# Power.net
KiCad netlist of a schematic drawn in Altium Designer
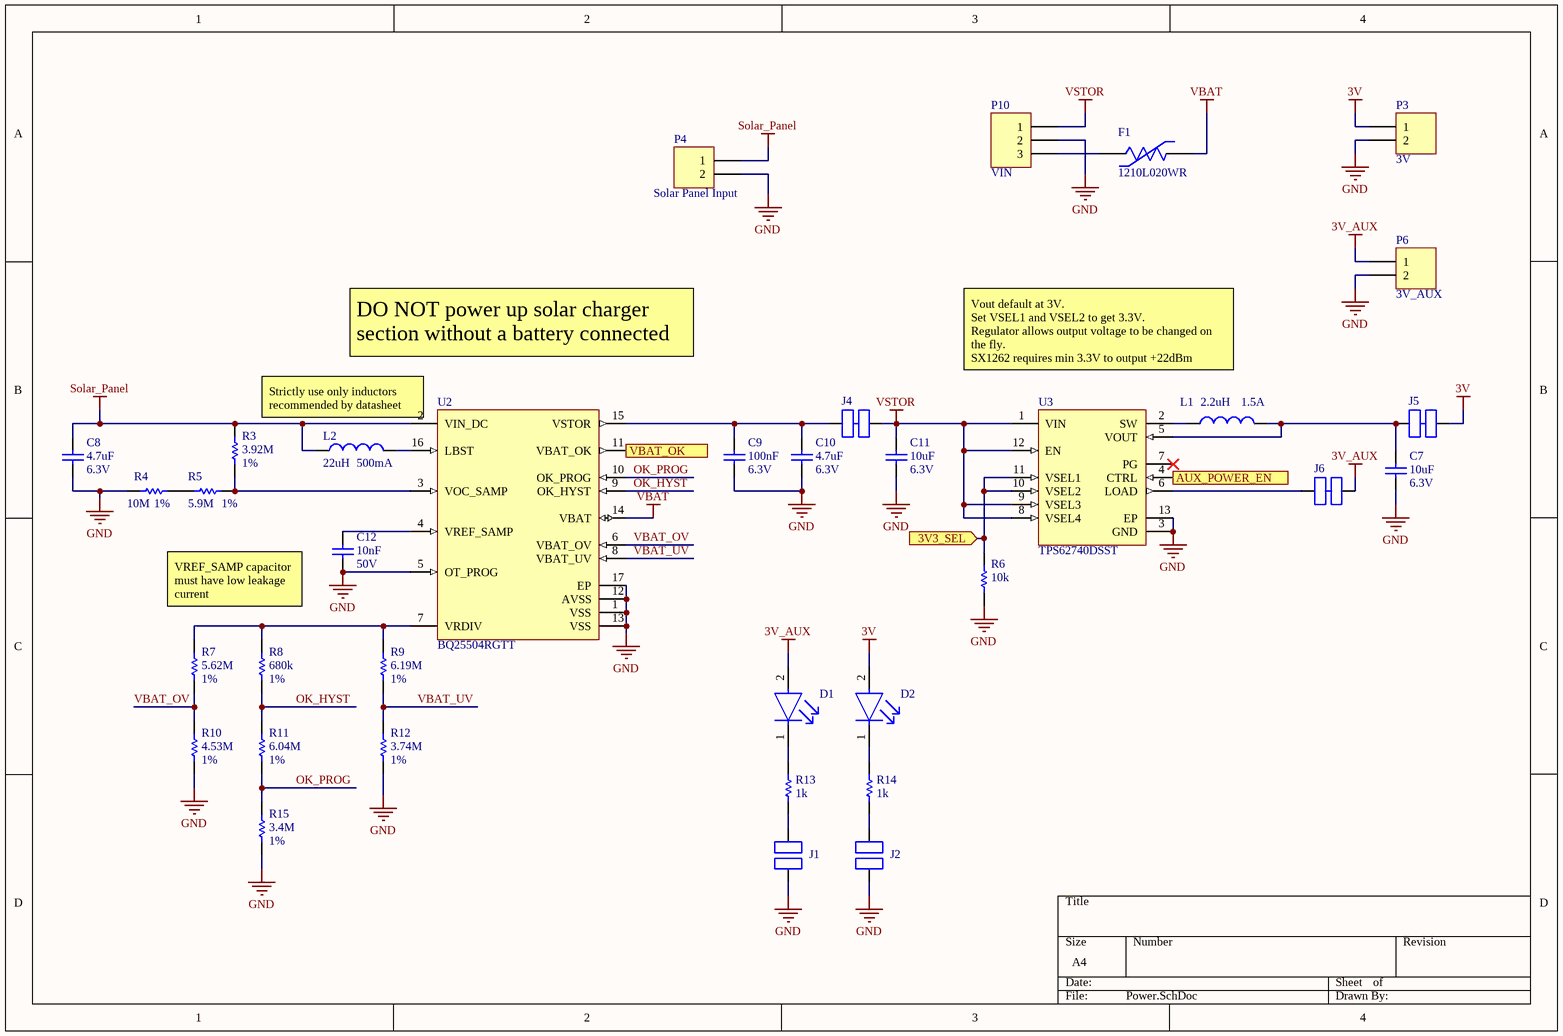
[diagram p0: Power.SchDoc]

(export (version "E")
  (design (tool "Eeschema 10.0.6"))
  (components
    (comp (ref "C7")
      (value "10uF")
      (footprint "0603 (1608M)")
      (description "Capacitor")
      (fields (field (name "VOLTAGE") "6.3V") (field (name "Comment") "Cap"))
      (libsource (lib "components") (part "Cap"))
    )
    (comp (ref "C8")
      (value "4.7uF")
      (footprint "0603 (1608M)")
      (description "Capacitor")
      (fields (field (name "VOLTAGE") "6.3V") (field (name "Comment") "Cap"))
      (libsource (lib "components") (part "Cap"))
    )
    (comp (ref "C9")
      (value "100nF")
      (footprint "0603 (1608M)")
      (description "Capacitor")
      (fields (field (name "VOLTAGE") "6.3V") (field (name "Comment") "Cap"))
      (libsource (lib "components") (part "Cap"))
    )
    (comp (ref "C10")
      (value "4.7uF")
      (footprint "0603 (1608M)")
      (description "Capacitor")
      (fields (field (name "VOLTAGE") "6.3V") (field (name "Comment") "Cap"))
      (libsource (lib "components") (part "Cap"))
    )
    (comp (ref "C11")
      (value "10uF")
      (footprint "0603 (1608M)")
      (description "Capacitor")
      (fields (field (name "VOLTAGE") "6.3V") (field (name "Comment") "Cap"))
      (libsource (lib "components") (part "Cap"))
    )
    (comp (ref "C12")
      (value "10nF")
      (footprint "0603 (1608M)")
      (description "Capacitor")
      (fields (field (name "VOLTAGE") "50V") (field (name "Comment") "Cap"))
      (libsource (lib "components") (part "Cap"))
    )
    (comp (ref "D1")
      (value "SML-D12P8WT86")
      (footprint "FP-SML-D12-MFG")
      (description "LED GREEN DIFFUSED 0603 SMD")
      (fields
        (field (name "OCTOPART") "https://octopart.com/sml-d12p8wt86-rohm-9289138")
        (field (name "MANUFACTURER") "Rohm")
      )
      (libsource (lib "Altium Content Vault") (part "8706943c75ba83719d021d2fdc84c58"))
    )
    (comp (ref "D2")
      (value "SML-D12P8WT86")
      (footprint "FP-SML-D12-MFG")
      (description "LED GREEN DIFFUSED 0603 SMD")
      (fields
        (field (name "OCTOPART") "https://octopart.com/sml-d12p8wt86-rohm-9289138")
        (field (name "MANUFACTURER") "Rohm")
      )
      (libsource (lib "Altium Content Vault") (part "8706943c75ba83719d021d2fdc84c58"))
    )
    (comp (ref "F1")
      (value "1210L020WR")
      (footprint "FP-1210L-MFG")
      (description "PTC Resettable Fuse 0.2A(hold) 0.4A(trip) 30VDC 10A 0.6W 0.02s 0.8Ohm SMD Solder Pad 1210 T/R")
      (fields (field (name "OCTOPART") "https://octopart.com/1210l020wr-littelfuse-673644"))
      (libsource (lib "Altium Content Vault") (part "fc31388045fc42ab786d6d00b506e9f"))
    )
    (comp (ref "J1")
      (value "Open Jumper")
      (footprint "Jumper (Open)")
      (libsource (lib "components") (part "Jumper (Open)"))
    )
    (comp (ref "J2")
      (value "Open Jumper")
      (footprint "Jumper (Open)")
      (libsource (lib "components") (part "Jumper (Open)"))
    )
    (comp (ref "J4")
      (value "Closed Jumper")
      (footprint "Jumper (Close)")
      (libsource (lib "components") (part "Jumper (Closed)"))
    )
    (comp (ref "J5")
      (value "Closed Jumper")
      (footprint "Jumper (Close)")
      (libsource (lib "components") (part "Jumper (Closed)"))
    )
    (comp (ref "J6")
      (value "Closed Jumper")
      (footprint "Jumper (Close)")
      (libsource (lib "components") (part "Jumper (Closed)"))
    )
    (comp (ref "L1")
      (value "74479787222")
      (footprint "SMD-1008")
      (description "Power Multilayer Inductor WE-PMI, L=2.20 µH")
      (fields
        (field (name "MANUFACTURER") "Wuerth Elektronik")
        (field (name "PARAMETER 1") "2.2uH")
        (field (name "PARAMETER 2") "1.5A")
      )
      (libsource (lib "Altium Content Vault") (part "PAS-IND-INDUCTOR-2"))
    )
    (comp (ref "L2")
      (value "744025220")
      (footprint "WE-TPC 2828")
      (description "SMD Shielded Tiny Power Inductor WE-TPC, L=22.0 µH")
      (fields
        (field (name "MANUFACTURER") "Wuerth Elektronik")
        (field (name "INDUCTANCE") "22uH")
        (field (name "CURRENT") "500mA")
      )
      (libsource (lib "Altium Content Vault") (part "PAS-IND-INDUCTOR-2"))
    )
    (comp (ref "P3")
      (value "3V")
      (footprint "HDR1X2")
      (description "Header, 2-Pin")
      (fields (field (name "PUBLISHER") "Altium Limited"))
      (libsource (lib "Miscellaneous Connectors") (part "Header 2"))
    )
    (comp (ref "P4")
      (value "Solar Panel Input")
      (footprint "HDR1X2")
      (fields (field (name "PUBLISHER") "Altium Limited"))
      (libsource (lib "") (part "Header 2_1"))
    )
    (comp (ref "P6")
      (value "3V_AUX")
      (footprint "HDR1X2")
      (description "Header, 2-Pin")
      (fields (field (name "PUBLISHER") "Altium Limited"))
      (libsource (lib "Miscellaneous Connectors") (part "Header 2"))
    )
    (comp (ref "P10")
      (value "VIN")
      (footprint "HDR1X3")
      (description "Header, 3-Pin")
      (fields (field (name "PUBLISHER") "Altium Limited"))
      (libsource (lib "Miscellaneous Connectors") (part "Header 3"))
    )
    (comp (ref "R3")
      (value "3.92M")
      (footprint "0603 (1608M)")
      (description "Resistor")
      (fields (field (name "TOLERANCE") "1%") (field (name "PUBLISHER") "Altium Limited"))
      (libsource (lib "components") (part "Resistor"))
    )
    (comp (ref "R4")
      (value "10M")
      (footprint "0603 (1608M)")
      (description "Resistor")
      (fields (field (name "TOLERANCE") "1%") (field (name "PUBLISHER") "Altium Limited"))
      (libsource (lib "components") (part "Resistor"))
    )
    (comp (ref "R5")
      (value "5.9M")
      (footprint "0603 (1608M)")
      (description "Resistor")
      (fields (field (name "TOLERANCE") "1%") (field (name "PUBLISHER") "Altium Limited"))
      (libsource (lib "components") (part "Resistor"))
    )
    (comp (ref "R6")
      (value "10k")
      (footprint "0603 (1608M)")
      (description "Resistor")
      (fields (field (name "TOLERANCE") "5%") (field (name "PUBLISHER") "Altium Limited"))
      (libsource (lib "components") (part "Resistor"))
    )
    (comp (ref "R7")
      (value "5.62M")
      (footprint "0603 (1608M)")
      (description "Resistor")
      (fields (field (name "TOLERANCE") "1%") (field (name "PUBLISHER") "Altium Limited"))
      (libsource (lib "components") (part "Resistor"))
    )
    (comp (ref "R8")
      (value "680k")
      (footprint "0603 (1608M)")
      (description "Resistor")
      (fields (field (name "TOLERANCE") "1%") (field (name "PUBLISHER") "Altium Limited"))
      (libsource (lib "components") (part "Resistor"))
    )
    (comp (ref "R9")
      (value "6.19M")
      (footprint "0603 (1608M)")
      (description "Resistor")
      (fields (field (name "TOLERANCE") "1%") (field (name "PUBLISHER") "Altium Limited"))
      (libsource (lib "components") (part "Resistor"))
    )
    (comp (ref "R10")
      (value "4.53M")
      (footprint "0603 (1608M)")
      (description "Resistor")
      (fields (field (name "TOLERANCE") "1%") (field (name "PUBLISHER") "Altium Limited"))
      (libsource (lib "components") (part "Resistor"))
    )
    (comp (ref "R11")
      (value "6.04M")
      (footprint "0603 (1608M)")
      (description "Resistor")
      (fields (field (name "TOLERANCE") "1%") (field (name "PUBLISHER") "Altium Limited"))
      (libsource (lib "components") (part "Resistor"))
    )
    (comp (ref "R12")
      (value "3.74M")
      (footprint "0603 (1608M)")
      (description "Resistor")
      (fields (field (name "TOLERANCE") "1%") (field (name "PUBLISHER") "Altium Limited"))
      (libsource (lib "components") (part "Resistor"))
    )
    (comp (ref "R13")
      (value "1k")
      (footprint "0603 (1608M)")
      (description "Resistor")
      (fields (field (name "TOLERANCE") "5%") (field (name "PUBLISHER") "Altium Limited"))
      (libsource (lib "components") (part "Resistor"))
    )
    (comp (ref "R14")
      (value "1k")
      (footprint "0603 (1608M)")
      (description "Resistor")
      (fields (field (name "TOLERANCE") "5%") (field (name "PUBLISHER") "Altium Limited"))
      (libsource (lib "components") (part "Resistor"))
    )
    (comp (ref "R15")
      (value "3.4M")
      (footprint "0603 (1608M)")
      (description "Resistor")
      (fields (field (name "TOLERANCE") "1%") (field (name "PUBLISHER") "Altium Limited"))
      (libsource (lib "components") (part "Resistor"))
    )
    (comp (ref "U2")
      (value "BQ25504RGTT")
      (footprint "RGT0016C_V")
      (fields (field (name "MANUFACTURER") "Texas Instruments"))
      (libsource (lib "Altium Content Vault") (part "TI-BQ25504RGT16-1700X1700TP"))
    )
    (comp (ref "U3")
      (value "TPS62740DSST")
      (footprint "DSS0012A_V")
      (fields (field (name "PARTNUMBER") "TPS62740"))
      (libsource (lib "Altium Content Vault") (part "TI-TPS62740_2-WSON-12"))
    )
  )
  (nets
    (net (code "1") (name "/3V3_SEL") (class "Default")
      (node (ref "R6") (pin "2") (pinfunction "2_2") (pintype "passive"))
      (node (ref "U3") (pin "10") (pinfunction "VSEL2_10") (pintype "input"))
      (node (ref "U3") (pin "11") (pinfunction "VSEL1_11") (pintype "input"))
    )
    (net (code "2") (name "/AUX_POWER_EN") (class "Default")
      (node (ref "U3") (pin "4") (pinfunction "CTRL_4") (pintype "input"))
    )
    (net (code "3") (name "/OK_HYST") (class "Default")
      (node (ref "R11") (pin "2") (pinfunction "2_2") (pintype "passive"))
      (node (ref "R8") (pin "1") (pinfunction "1_1") (pintype "passive"))
      (node (ref "U2") (pin "9") (pinfunction "OK_HYST_9") (pintype "input"))
    )
    (net (code "4") (name "/OK_PROG") (class "Default")
      (node (ref "R11") (pin "1") (pinfunction "1_1") (pintype "passive"))
      (node (ref "R15") (pin "2") (pinfunction "2_2") (pintype "passive"))
      (node (ref "U2") (pin "10") (pinfunction "OK_PROG_10") (pintype "input"))
    )
    (net (code "5") (name "/VBAT_OK") (class "Default")
      (node (ref "U2") (pin "11") (pinfunction "VBAT_OK_11") (pintype "output"))
    )
    (net (code "6") (name "/VBAT_OV") (class "Default")
      (node (ref "R10") (pin "2") (pinfunction "2_2") (pintype "passive"))
      (node (ref "R7") (pin "1") (pinfunction "1_1") (pintype "passive"))
      (node (ref "U2") (pin "6") (pinfunction "VBAT_OV_6") (pintype "input"))
    )
    (net (code "7") (name "/VBAT_UV") (class "Default")
      (node (ref "R12") (pin "2") (pinfunction "2_2") (pintype "passive"))
      (node (ref "R9") (pin "1") (pinfunction "1_1") (pintype "passive"))
      (node (ref "U2") (pin "8") (pinfunction "VBAT_UV_8") (pintype "input"))
    )
    (net (code "8") (name "3V") (class "Default")
      (node (ref "D2") (pin "2") (pinfunction "A_2") (pintype "passive"))
      (node (ref "J5") (pin "2") (pinfunction "2_2") (pintype "passive"))
      (node (ref "P3") (pin "1") (pinfunction "1_1") (pintype "passive"))
    )
    (net (code "9") (name "3V_AUX") (class "Default")
      (node (ref "D1") (pin "2") (pinfunction "A_2") (pintype "passive"))
      (node (ref "J6") (pin "2") (pinfunction "2_2") (pintype "passive"))
      (node (ref "P6") (pin "1") (pinfunction "1_1") (pintype "passive"))
    )
    (net (code "10") (name "GND") (class "Default")
      (node (ref "C10") (pin "1") (pinfunction "1_1") (pintype "passive"))
      (node (ref "C11") (pin "1") (pinfunction "1_1") (pintype "passive"))
      (node (ref "C12") (pin "1") (pinfunction "1_1") (pintype "passive"))
      (node (ref "C7") (pin "1") (pinfunction "1_1") (pintype "passive"))
      (node (ref "C8") (pin "1") (pinfunction "1_1") (pintype "passive"))
      (node (ref "C9") (pin "1") (pinfunction "1_1") (pintype "passive"))
      (node (ref "J1") (pin "1") (pinfunction "1_1") (pintype "passive"))
      (node (ref "J2") (pin "1") (pinfunction "1_1") (pintype "passive"))
      (node (ref "P10") (pin "2") (pinfunction "2_2") (pintype "passive"))
      (node (ref "P3") (pin "2") (pinfunction "2_2") (pintype "passive"))
      (node (ref "P4") (pin "2") (pinfunction "2_2") (pintype "passive"))
      (node (ref "P6") (pin "2") (pinfunction "2_2") (pintype "passive"))
      (node (ref "R10") (pin "1") (pinfunction "1_1") (pintype "passive"))
      (node (ref "R12") (pin "1") (pinfunction "1_1") (pintype "passive"))
      (node (ref "R15") (pin "1") (pinfunction "1_1") (pintype "passive"))
      (node (ref "R4") (pin "1") (pinfunction "1_1") (pintype "passive"))
      (node (ref "R6") (pin "1") (pinfunction "1_1") (pintype "passive"))
      (node (ref "U2") (pin "1") (pinfunction "VSS_1") (pintype "power_in"))
      (node (ref "U2") (pin "12") (pinfunction "AVSS_12") (pintype "power_in"))
      (node (ref "U2") (pin "13") (pinfunction "VSS_13") (pintype "power_in"))
      (node (ref "U2") (pin "17") (pinfunction "EP_17") (pintype "passive"))
      (node (ref "U2") (pin "5") (pinfunction "OT_PROG_5") (pintype "input"))
      (node (ref "U3") (pin "13") (pinfunction "EP_13") (pintype "power_in"))
      (node (ref "U3") (pin "3") (pinfunction "GND_3") (pintype "power_in"))
    )
    (net (code "11") (name "Net-(D1-C)") (class "Default")
      (node (ref "D1") (pin "1") (pinfunction "C_1") (pintype "passive"))
      (node (ref "R13") (pin "2") (pinfunction "2_2") (pintype "passive"))
    )
    (net (code "12") (name "Net-(D2-C)") (class "Default")
      (node (ref "D2") (pin "1") (pinfunction "C_1") (pintype "passive"))
      (node (ref "R14") (pin "2") (pinfunction "2_2") (pintype "passive"))
    )
    (net (code "13") (name "Net-(F1-Pad1)") (class "Default")
      (node (ref "F1") (pin "1") (pinfunction "1_1") (pintype "passive"))
      (node (ref "P10") (pin "3") (pinfunction "3_3") (pintype "passive"))
    )
    (net (code "14") (name "Net-(J1-Pad2)") (class "Default")
      (node (ref "J1") (pin "2") (pinfunction "2_2") (pintype "passive"))
      (node (ref "R13") (pin "1") (pinfunction "1_1") (pintype "passive"))
    )
    (net (code "15") (name "Net-(J2-Pad2)") (class "Default")
      (node (ref "J2") (pin "2") (pinfunction "2_2") (pintype "passive"))
      (node (ref "R14") (pin "1") (pinfunction "1_1") (pintype "passive"))
    )
    (net (code "16") (name "Net-(R4-Pad2)") (class "Default")
      (node (ref "R4") (pin "2") (pinfunction "2_2") (pintype "passive"))
      (node (ref "R5") (pin "1") (pinfunction "1_1") (pintype "passive"))
    )
    (net (code "17") (name "Net-(U2-LBST)") (class "Default")
      (node (ref "L2") (pin "2") (pinfunction "2_2") (pintype "passive"))
      (node (ref "U2") (pin "16") (pinfunction "LBST_16") (pintype "input"))
    )
    (net (code "18") (name "Net-(U2-VOC_SAMP)") (class "Default")
      (node (ref "R3") (pin "1") (pinfunction "1_1") (pintype "passive"))
      (node (ref "R5") (pin "2") (pinfunction "2_2") (pintype "passive"))
      (node (ref "U2") (pin "3") (pinfunction "VOC_SAMP_3") (pintype "input"))
    )
    (net (code "19") (name "Net-(U2-VRDIV)") (class "Default")
      (node (ref "R7") (pin "2") (pinfunction "2_2") (pintype "passive"))
      (node (ref "R8") (pin "2") (pinfunction "2_2") (pintype "passive"))
      (node (ref "R9") (pin "2") (pinfunction "2_2") (pintype "passive"))
      (node (ref "U2") (pin "7") (pinfunction "VRDIV_7") (pintype "power_in"))
    )
    (net (code "20") (name "Net-(U2-VREF_SAMP)") (class "Default")
      (node (ref "C12") (pin "2") (pinfunction "2_2") (pintype "passive"))
      (node (ref "U2") (pin "4") (pinfunction "VREF_SAMP_4") (pintype "input"))
    )
    (net (code "21") (name "Net-(U2-VSTOR)") (class "Default")
      (node (ref "C10") (pin "2") (pinfunction "2_2") (pintype "passive"))
      (node (ref "C9") (pin "2") (pinfunction "2_2") (pintype "passive"))
      (node (ref "J4") (pin "1") (pinfunction "1_1") (pintype "passive"))
      (node (ref "U2") (pin "15") (pinfunction "VSTOR_15") (pintype "output"))
    )
    (net (code "22") (name "Net-(U3-LOAD)") (class "Default")
      (node (ref "J6") (pin "1") (pinfunction "1_1") (pintype "passive"))
      (node (ref "U3") (pin "6") (pinfunction "LOAD_6") (pintype "output"))
    )
    (net (code "23") (name "Net-(U3-SW)") (class "Default")
      (node (ref "L1") (pin "1") (pinfunction "1_1") (pintype "passive"))
      (node (ref "U3") (pin "2") (pinfunction "SW_2") (pintype "power_in"))
    )
    (net (code "24") (name "Net-(U3-VOUT)") (class "Default")
      (node (ref "C7") (pin "2") (pinfunction "2_2") (pintype "passive"))
      (node (ref "J5") (pin "1") (pinfunction "1_1") (pintype "passive"))
      (node (ref "L1") (pin "2") (pinfunction "2_2") (pintype "passive"))
      (node (ref "U3") (pin "5") (pinfunction "VOUT_5") (pintype "input"))
    )
    (net (code "25") (name "Solar_Panel") (class "Default")
      (node (ref "C8") (pin "2") (pinfunction "2_2") (pintype "passive"))
      (node (ref "L2") (pin "1") (pinfunction "1_1") (pintype "passive"))
      (node (ref "P4") (pin "1") (pinfunction "1_1") (pintype "passive"))
      (node (ref "R3") (pin "2") (pinfunction "2_2") (pintype "passive"))
      (node (ref "U2") (pin "2") (pinfunction "VIN_DC_2") (pintype "power_in"))
    )
    (net (code "26") (name "VBAT") (class "Default")
      (node (ref "F1") (pin "2") (pinfunction "2_2") (pintype "passive"))
      (node (ref "U2") (pin "14") (pinfunction "VBAT_14") (pintype "bidirectional"))
    )
    (net (code "27") (name "VSTOR") (class "Default")
      (node (ref "C11") (pin "2") (pinfunction "2_2") (pintype "passive"))
      (node (ref "J4") (pin "2") (pinfunction "2_2") (pintype "passive"))
      (node (ref "P10") (pin "1") (pinfunction "1_1") (pintype "passive"))
      (node (ref "U3") (pin "1") (pinfunction "VIN_1") (pintype "power_in"))
      (node (ref "U3") (pin "12") (pinfunction "EN_12") (pintype "input"))
      (node (ref "U3") (pin "8") (pinfunction "VSEL4_8") (pintype "input"))
      (node (ref "U3") (pin "9") (pinfunction "VSEL3_9") (pintype "input"))
    )
    (net (code "28") (name "unconnected-(U3-PG-Pad7)") (class "Default")
      (node (ref "U3") (pin "7") (pinfunction "PG_7") (pintype "tri_state+no_connect"))
    )
  )
)
